# power.net
KiCad netlist of a schematic drawn in EAGLE
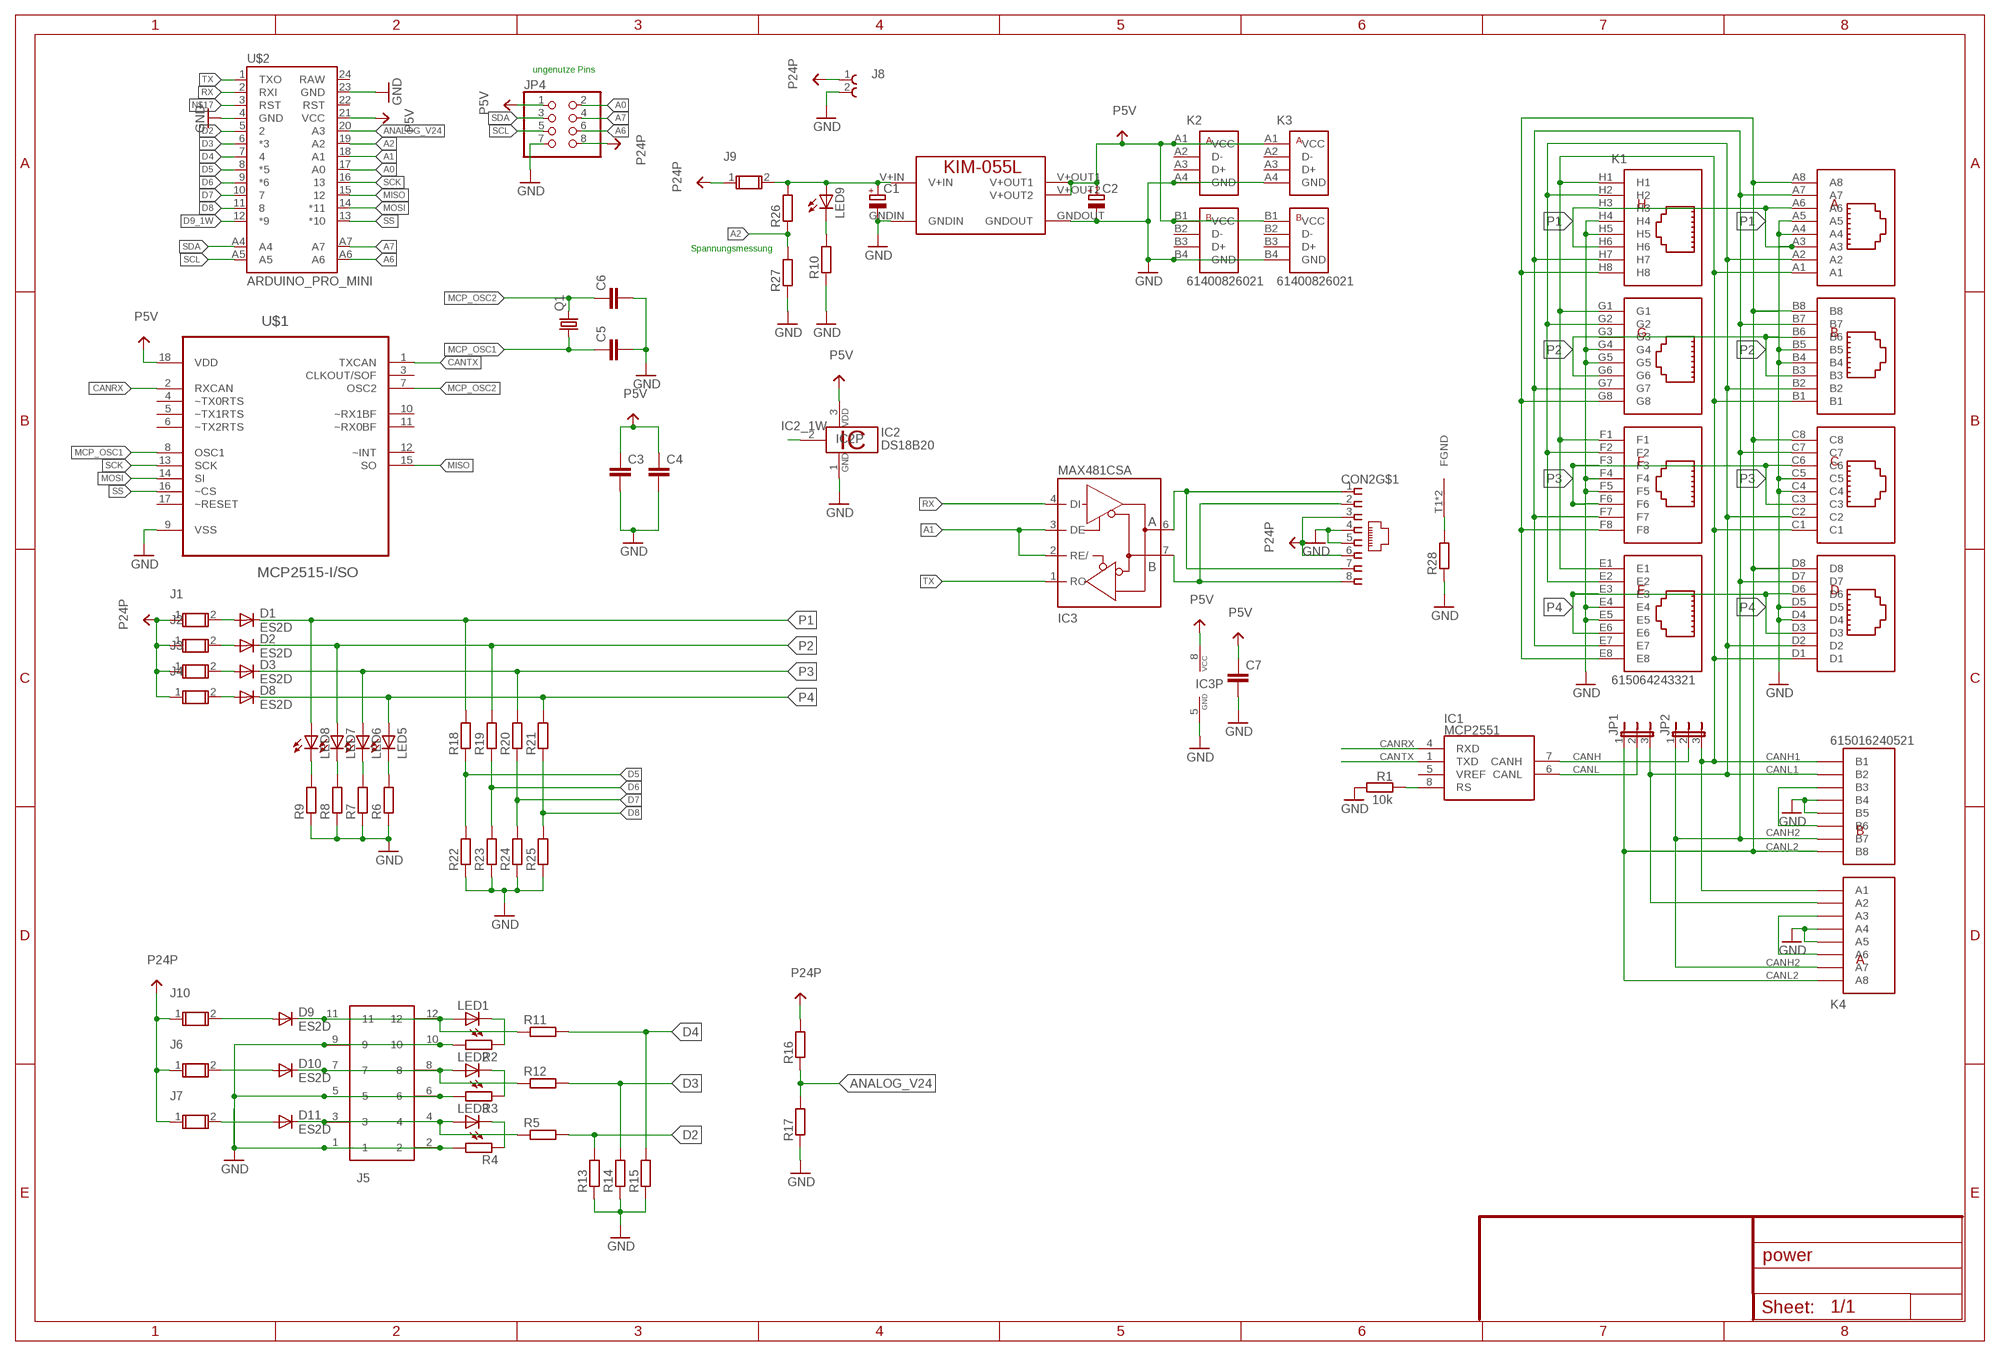
[diagram p0: schematic, sheet 1]

(export (version "E")
  (design (tool "Eeschema 10.0.6"))
  (components
    (comp (ref "C1")
      (value "CPOL-EUE5-10.5")
      (footprint "eagle-import:E5-10,5")
      (libsource (lib "eagle-import") (part "CPOL-EUE5-10.5"))
    )
    (comp (ref "C2")
      (value "CPOL-EUE5-10.5")
      (footprint "eagle-import:E5-10,5")
      (libsource (lib "eagle-import") (part "CPOL-EUE5-10.5"))
    )
    (comp (ref "C3")
      (value "C-EUC0805")
      (footprint "eagle-import:C0805")
      (libsource (lib "eagle-import") (part "C-EUC0805"))
    )
    (comp (ref "C4")
      (value "C-EUC0805")
      (footprint "eagle-import:C0805")
      (libsource (lib "eagle-import") (part "C-EUC0805"))
    )
    (comp (ref "C5")
      (value "C-EUC0805")
      (footprint "eagle-import:C0805")
      (libsource (lib "eagle-import") (part "C-EUC0805"))
    )
    (comp (ref "C6")
      (value "C-EUC0805")
      (footprint "eagle-import:C0805")
      (libsource (lib "eagle-import") (part "C-EUC0805"))
    )
    (comp (ref "C7")
      (value "C-EUC0805")
      (footprint "eagle-import:C0805")
      (libsource (lib "eagle-import") (part "C-EUC0805"))
    )
    (comp (ref "CON2")
      (value "MEBP_8-8G")
      (footprint "eagle-import:MEBP")
      (libsource (lib "eagle-import") (part "MEBP_8-8G"))
    )
    (comp (ref "D1")
      (value "ES2D")
      (footprint "eagle-import:SMB")
      (libsource (lib "eagle-import") (part "ES2D"))
    )
    (comp (ref "D2")
      (value "ES2D")
      (footprint "eagle-import:SMB")
      (libsource (lib "eagle-import") (part "ES2D"))
    )
    (comp (ref "D3")
      (value "ES2D")
      (footprint "eagle-import:SMB")
      (libsource (lib "eagle-import") (part "ES2D"))
    )
    (comp (ref "D8")
      (value "ES2D")
      (footprint "eagle-import:SMB")
      (libsource (lib "eagle-import") (part "ES2D"))
    )
    (comp (ref "D9")
      (value "ES2D")
      (footprint "eagle-import:SMB")
      (libsource (lib "eagle-import") (part "ES2D"))
    )
    (comp (ref "D10")
      (value "ES2D")
      (footprint "eagle-import:SMB")
      (libsource (lib "eagle-import") (part "ES2D"))
    )
    (comp (ref "D11")
      (value "ES2D")
      (footprint "eagle-import:SMB")
      (libsource (lib "eagle-import") (part "ES2D"))
    )
    (comp (ref "IC1")
      (value "MCP2551")
      (footprint "eagle-import:SO-8")
      (libsource (lib "eagle-import") (part "MCP2551"))
    )
    (comp (ref "IC2")
      (value "DS18B20")
      (footprint "eagle-import:TO92-")
      (libsource (lib "eagle-import") (part "DS18B20"))
    )
    (comp (ref "IC3")
      (value "MAX481CSA")
      (footprint "eagle-import:SO08")
      (fields (field (name "MF") "MAXIM"))
      (libsource (lib "eagle-import") (part "MAX481CSA"))
    )
    (comp (ref "J1")
      (value "696101000002")
      (footprint "eagle-import:696101000002")
      (libsource (lib "eagle-import") (part "696101000002"))
    )
    (comp (ref "J2")
      (value "696101000002")
      (footprint "eagle-import:696101000002")
      (libsource (lib "eagle-import") (part "696101000002"))
    )
    (comp (ref "J3")
      (value "696101000002")
      (footprint "eagle-import:696101000002")
      (libsource (lib "eagle-import") (part "696101000002"))
    )
    (comp (ref "J4")
      (value "696101000002")
      (footprint "eagle-import:696101000002")
      (libsource (lib "eagle-import") (part "696101000002"))
    )
    (comp (ref "J5")
      (value "691332510012")
      (footprint "eagle-import:691332510012")
      (libsource (lib "eagle-import") (part "691332510012"))
    )
    (comp (ref "J6")
      (value "696101000002")
      (footprint "eagle-import:696101000002")
      (libsource (lib "eagle-import") (part "696101000002"))
    )
    (comp (ref "J7")
      (value "696101000002")
      (footprint "eagle-import:696101000002")
      (libsource (lib "eagle-import") (part "696101000002"))
    )
    (comp (ref "J8")
      (value "691312510002")
      (footprint "eagle-import:691312510002")
      (libsource (lib "eagle-import") (part "691312510002"))
    )
    (comp (ref "J9")
      (value "696101000002")
      (footprint "eagle-import:696101000002")
      (libsource (lib "eagle-import") (part "696101000002"))
    )
    (comp (ref "J10")
      (value "696101000002")
      (footprint "eagle-import:696101000002")
      (libsource (lib "eagle-import") (part "696101000002"))
    )
    (comp (ref "JP1")
      (value "JP2E")
      (footprint "eagle-import:JP2")
      (libsource (lib "eagle-import") (part "JP2E"))
    )
    (comp (ref "JP2")
      (value "JP2E")
      (footprint "eagle-import:JP2")
      (libsource (lib "eagle-import") (part "JP2E"))
    )
    (comp (ref "JP4")
      (value "PINHD-2X4")
      (footprint "eagle-import:2X04")
      (libsource (lib "eagle-import") (part "PINHD-2X4"))
    )
    (comp (ref "K1")
      (value "615064243321")
      (footprint "eagle-import:615064243321")
      (libsource (lib "eagle-import") (part "615064243321"))
    )
    (comp (ref "K2")
      (value "61400826021")
      (footprint "eagle-import:61400826021")
      (libsource (lib "eagle-import") (part "61400826021"))
    )
    (comp (ref "K3")
      (value "61400826021")
      (footprint "eagle-import:61400826021")
      (libsource (lib "eagle-import") (part "61400826021"))
    )
    (comp (ref "K4")
      (value "615016240521")
      (footprint "eagle-import:615016240521")
      (libsource (lib "eagle-import") (part "615016240521"))
    )
    (comp (ref "LED1")
      (value "LED3MM")
      (footprint "eagle-import:LED3MM")
      (libsource (lib "eagle-import") (part "LED3MM"))
    )
    (comp (ref "LED2")
      (value "LED3MM")
      (footprint "eagle-import:LED3MM")
      (libsource (lib "eagle-import") (part "LED3MM"))
    )
    (comp (ref "LED3")
      (value "LED3MM")
      (footprint "eagle-import:LED3MM")
      (libsource (lib "eagle-import") (part "LED3MM"))
    )
    (comp (ref "LED5")
      (value "LED3MM")
      (footprint "eagle-import:LED3MM")
      (libsource (lib "eagle-import") (part "LED3MM"))
    )
    (comp (ref "LED6")
      (value "LED3MM")
      (footprint "eagle-import:LED3MM")
      (libsource (lib "eagle-import") (part "LED3MM"))
    )
    (comp (ref "LED7")
      (value "LED3MM")
      (footprint "eagle-import:LED3MM")
      (libsource (lib "eagle-import") (part "LED3MM"))
    )
    (comp (ref "LED8")
      (value "LED3MM")
      (footprint "eagle-import:LED3MM")
      (libsource (lib "eagle-import") (part "LED3MM"))
    )
    (comp (ref "LED9")
      (value "LED3MM")
      (footprint "eagle-import:LED3MM")
      (libsource (lib "eagle-import") (part "LED3MM"))
    )
    (comp (ref "MOD1")
      (value "KIM-055L")
      (footprint "eagle-import:KIM-055L")
      (libsource (lib "eagle-import") (part "KIM-055L"))
    )
    (comp (ref "Q1")
      (value "CRYSTALHC49S")
      (footprint "eagle-import:HC49_S")
      (libsource (lib "eagle-import") (part "CRYSTALHC49S"))
    )
    (comp (ref "R1")
      (value "10k")
      (footprint "eagle-import:R0603")
      (libsource (lib "eagle-import") (part "R-EU_R0603"))
    )
    (comp (ref "R2")
      (value "R-EU_R0805")
      (footprint "eagle-import:R0805")
      (libsource (lib "eagle-import") (part "schlager_passiv_R-EU_R0805"))
    )
    (comp (ref "R3")
      (value "R-EU_R0805")
      (footprint "eagle-import:R0805")
      (libsource (lib "eagle-import") (part "schlager_passiv_R-EU_R0805"))
    )
    (comp (ref "R4")
      (value "R-EU_R0805")
      (footprint "eagle-import:R0805")
      (libsource (lib "eagle-import") (part "schlager_passiv_R-EU_R0805"))
    )
    (comp (ref "R5")
      (value "R-EU_R0805")
      (footprint "eagle-import:R0805")
      (libsource (lib "eagle-import") (part "schlager_passiv_R-EU_R0805"))
    )
    (comp (ref "R6")
      (value "R-EU_R0805")
      (footprint "eagle-import:R0805")
      (libsource (lib "eagle-import") (part "schlager_passiv_R-EU_R0805"))
    )
    (comp (ref "R7")
      (value "R-EU_R0805")
      (footprint "eagle-import:R0805")
      (libsource (lib "eagle-import") (part "schlager_passiv_R-EU_R0805"))
    )
    (comp (ref "R8")
      (value "R-EU_R0805")
      (footprint "eagle-import:R0805")
      (libsource (lib "eagle-import") (part "schlager_passiv_R-EU_R0805"))
    )
    (comp (ref "R9")
      (value "R-EU_R0805")
      (footprint "eagle-import:R0805")
      (libsource (lib "eagle-import") (part "schlager_passiv_R-EU_R0805"))
    )
    (comp (ref "R10")
      (value "R-EU_R0805")
      (footprint "eagle-import:R0805")
      (libsource (lib "eagle-import") (part "schlager_passiv_R-EU_R0805"))
    )
    (comp (ref "R11")
      (value "R-EU_R0805")
      (footprint "eagle-import:R0805")
      (libsource (lib "eagle-import") (part "schlager_passiv_R-EU_R0805"))
    )
    (comp (ref "R12")
      (value "R-EU_R0805")
      (footprint "eagle-import:R0805")
      (libsource (lib "eagle-import") (part "schlager_passiv_R-EU_R0805"))
    )
    (comp (ref "R13")
      (value "R-EU_R0805")
      (footprint "eagle-import:R0805")
      (libsource (lib "eagle-import") (part "schlager_passiv_R-EU_R0805"))
    )
    (comp (ref "R14")
      (value "R-EU_R0805")
      (footprint "eagle-import:R0805")
      (libsource (lib "eagle-import") (part "schlager_passiv_R-EU_R0805"))
    )
    (comp (ref "R15")
      (value "R-EU_R0805")
      (footprint "eagle-import:R0805")
      (libsource (lib "eagle-import") (part "schlager_passiv_R-EU_R0805"))
    )
    (comp (ref "R16")
      (value "R-EU_R0805")
      (footprint "eagle-import:R0805")
      (libsource (lib "eagle-import") (part "schlager_passiv_R-EU_R0805"))
    )
    (comp (ref "R17")
      (value "R-EU_R0805")
      (footprint "eagle-import:R0805")
      (libsource (lib "eagle-import") (part "schlager_passiv_R-EU_R0805"))
    )
    (comp (ref "R18")
      (value "R-EU_R0805")
      (footprint "eagle-import:R0805")
      (libsource (lib "eagle-import") (part "schlager_passiv_R-EU_R0805"))
    )
    (comp (ref "R19")
      (value "R-EU_R0805")
      (footprint "eagle-import:R0805")
      (libsource (lib "eagle-import") (part "schlager_passiv_R-EU_R0805"))
    )
    (comp (ref "R20")
      (value "R-EU_R0805")
      (footprint "eagle-import:R0805")
      (libsource (lib "eagle-import") (part "schlager_passiv_R-EU_R0805"))
    )
    (comp (ref "R21")
      (value "R-EU_R0805")
      (footprint "eagle-import:R0805")
      (libsource (lib "eagle-import") (part "schlager_passiv_R-EU_R0805"))
    )
    (comp (ref "R22")
      (value "R-EU_R0805")
      (footprint "eagle-import:R0805")
      (libsource (lib "eagle-import") (part "schlager_passiv_R-EU_R0805"))
    )
    (comp (ref "R23")
      (value "R-EU_R0805")
      (footprint "eagle-import:R0805")
      (libsource (lib "eagle-import") (part "schlager_passiv_R-EU_R0805"))
    )
    (comp (ref "R24")
      (value "R-EU_R0805")
      (footprint "eagle-import:R0805")
      (libsource (lib "eagle-import") (part "schlager_passiv_R-EU_R0805"))
    )
    (comp (ref "R25")
      (value "R-EU_R0805")
      (footprint "eagle-import:R0805")
      (libsource (lib "eagle-import") (part "schlager_passiv_R-EU_R0805"))
    )
    (comp (ref "R26")
      (value "R-EU_R0805")
      (footprint "eagle-import:R0805")
      (libsource (lib "eagle-import") (part "schlager_passiv_R-EU_R0805"))
    )
    (comp (ref "R27")
      (value "R-EU_R0805")
      (footprint "eagle-import:R0805")
      (libsource (lib "eagle-import") (part "schlager_passiv_R-EU_R0805"))
    )
    (comp (ref "R28")
      (value "R-EU_R0805")
      (footprint "eagle-import:R0805")
      (libsource (lib "eagle-import") (part "schlager_passiv_R-EU_R0805"))
    )
    (comp (ref "U$1")
      (value "MCP2515-I/SO")
      (footprint "eagle-import:SOIC127P1034X264-18N")
      (libsource (lib "eagle-import") (part "MCP2515-I/SO"))
    )
    (comp (ref "U$2")
      (value "ARDUINO_PRO_MINI")
      (footprint "eagle-import:ARDUINO_PRO_MINI")
      (libsource (lib "eagle-import") (part "ARDUINO_PRO_MINI"))
    )
  )
  (nets
    (net (code "1") (name "/CANH") (class "Default")
      (node (ref "IC1") (pin "7") (pinfunction "CANH_7") (pintype "bidirectional"))
      (node (ref "JP2") (pin "2") (pinfunction "2_2") (pintype "passive"))
    )
    (net (code "2") (name "/CANH1") (class "Default")
      (node (ref "JP2") (pin "3") (pinfunction "3_3") (pintype "passive"))
      (node (ref "K1") (pin "A1") (pinfunction "A1_A1") (pintype "passive"))
      (node (ref "K1") (pin "B1") (pinfunction "B1_B1") (pintype "passive"))
      (node (ref "K1") (pin "C1") (pinfunction "C1_C1") (pintype "passive"))
      (node (ref "K1") (pin "D1") (pinfunction "D1_D1") (pintype "passive"))
      (node (ref "K1") (pin "E1") (pinfunction "E1_E1") (pintype "passive"))
      (node (ref "K1") (pin "F1") (pinfunction "F1_F1") (pintype "passive"))
      (node (ref "K1") (pin "G1") (pinfunction "G1_G1") (pintype "passive"))
      (node (ref "K1") (pin "H1") (pinfunction "H1_H1") (pintype "passive"))
      (node (ref "K4") (pin "A1") (pinfunction "A1_A1") (pintype "passive"))
      (node (ref "K4") (pin "B1") (pinfunction "B1_B1") (pintype "passive"))
    )
    (net (code "3") (name "/CANH2") (class "Default")
      (node (ref "JP2") (pin "1") (pinfunction "1_1") (pintype "passive"))
      (node (ref "K1") (pin "A7") (pinfunction "A7_A7") (pintype "passive"))
      (node (ref "K1") (pin "B7") (pinfunction "B7_B7") (pintype "passive"))
      (node (ref "K1") (pin "C7") (pinfunction "C7_C7") (pintype "passive"))
      (node (ref "K1") (pin "D7") (pinfunction "D7_D7") (pintype "passive"))
      (node (ref "K1") (pin "E7") (pinfunction "E7_E7") (pintype "passive"))
      (node (ref "K1") (pin "F7") (pinfunction "F7_F7") (pintype "passive"))
      (node (ref "K1") (pin "G7") (pinfunction "G7_G7") (pintype "passive"))
      (node (ref "K1") (pin "H7") (pinfunction "H7_H7") (pintype "passive"))
      (node (ref "K4") (pin "A7") (pinfunction "A7_A7") (pintype "passive"))
      (node (ref "K4") (pin "B7") (pinfunction "B7_B7") (pintype "passive"))
    )
    (net (code "4") (name "/CANL") (class "Default")
      (node (ref "IC1") (pin "6") (pinfunction "CANL_6") (pintype "bidirectional"))
      (node (ref "JP1") (pin "2") (pinfunction "2_2") (pintype "passive"))
    )
    (net (code "5") (name "/CANL1") (class "Default")
      (node (ref "JP1") (pin "3") (pinfunction "3_3") (pintype "passive"))
      (node (ref "K1") (pin "A2") (pinfunction "A2_A2") (pintype "passive"))
      (node (ref "K1") (pin "B2") (pinfunction "B2_B2") (pintype "passive"))
      (node (ref "K1") (pin "C2") (pinfunction "C2_C2") (pintype "passive"))
      (node (ref "K1") (pin "D2") (pinfunction "D2_D2") (pintype "passive"))
      (node (ref "K1") (pin "E2") (pinfunction "E2_E2") (pintype "passive"))
      (node (ref "K1") (pin "F2") (pinfunction "F2_F2") (pintype "passive"))
      (node (ref "K1") (pin "G2") (pinfunction "G2_G2") (pintype "passive"))
      (node (ref "K1") (pin "H2") (pinfunction "H2_H2") (pintype "passive"))
      (node (ref "K4") (pin "A2") (pinfunction "A2_A2") (pintype "passive"))
      (node (ref "K4") (pin "B2") (pinfunction "B2_B2") (pintype "passive"))
    )
    (net (code "6") (name "/CANL2") (class "Default")
      (node (ref "JP1") (pin "1") (pinfunction "1_1") (pintype "passive"))
      (node (ref "K1") (pin "A8") (pinfunction "A8_A8") (pintype "passive"))
      (node (ref "K1") (pin "B8") (pinfunction "B8_B8") (pintype "passive"))
      (node (ref "K1") (pin "C8") (pinfunction "C8_C8") (pintype "passive"))
      (node (ref "K1") (pin "D8") (pinfunction "D8_D8") (pintype "passive"))
      (node (ref "K1") (pin "E8") (pinfunction "E8_E8") (pintype "passive"))
      (node (ref "K1") (pin "F8") (pinfunction "F8_F8") (pintype "passive"))
      (node (ref "K1") (pin "G8") (pinfunction "G8_G8") (pintype "passive"))
      (node (ref "K1") (pin "H8") (pinfunction "H8_H8") (pintype "passive"))
      (node (ref "K4") (pin "A8") (pinfunction "A8_A8") (pintype "passive"))
      (node (ref "K4") (pin "B8") (pinfunction "B8_B8") (pintype "passive"))
    )
    (net (code "7") (name "A0") (class "Default")
      (node (ref "JP4") (pin "2") (pinfunction "2_2") (pintype "passive"))
      (node (ref "U$2") (pin "17") (pinfunction "A0_17") (pintype "bidirectional"))
    )
    (net (code "8") (name "A1") (class "Default")
      (node (ref "IC3") (pin "2") (pinfunction "RE/_2") (pintype "input"))
      (node (ref "IC3") (pin "3") (pinfunction "DE_3") (pintype "input"))
      (node (ref "U$2") (pin "18") (pinfunction "A1_18") (pintype "bidirectional"))
    )
    (net (code "9") (name "A2") (class "Default")
      (node (ref "R26") (pin "1") (pinfunction "1_1") (pintype "passive"))
      (node (ref "R27") (pin "2") (pinfunction "2_2") (pintype "passive"))
      (node (ref "U$2") (pin "19") (pinfunction "A2_19") (pintype "bidirectional"))
    )
    (net (code "10") (name "A6") (class "Default")
      (node (ref "JP4") (pin "6") (pinfunction "6_6") (pintype "passive"))
      (node (ref "U$2") (pin "A6") (pinfunction "A6_A6") (pintype "bidirectional"))
    )
    (net (code "11") (name "A7") (class "Default")
      (node (ref "JP4") (pin "4") (pinfunction "4_4") (pintype "passive"))
      (node (ref "U$2") (pin "A7") (pinfunction "A7_A7") (pintype "bidirectional"))
    )
    (net (code "12") (name "ANALOG_V24") (class "Default")
      (node (ref "R16") (pin "1") (pinfunction "1_1") (pintype "passive"))
      (node (ref "R17") (pin "2") (pinfunction "2_2") (pintype "passive"))
      (node (ref "U$2") (pin "20") (pinfunction "A3_20") (pintype "bidirectional"))
    )
    (net (code "13") (name "CANRX") (class "Default")
      (node (ref "IC1") (pin "4") (pinfunction "RXD_4") (pintype "bidirectional"))
      (node (ref "U$1") (pin "2") (pinfunction "RXCAN_2") (pintype "input"))
    )
    (net (code "14") (name "CANTX") (class "Default")
      (node (ref "IC1") (pin "1") (pinfunction "TXD_1") (pintype "bidirectional"))
      (node (ref "U$1") (pin "1") (pinfunction "TXCAN_1") (pintype "output"))
    )
    (net (code "15") (name "D2") (class "Default")
      (node (ref "R13") (pin "2") (pinfunction "2_2") (pintype "passive"))
      (node (ref "R5") (pin "2") (pinfunction "2_2") (pintype "passive"))
      (node (ref "U$2") (pin "5") (pinfunction "2_5") (pintype "bidirectional"))
    )
    (net (code "16") (name "D3") (class "Default")
      (node (ref "R12") (pin "2") (pinfunction "2_2") (pintype "passive"))
      (node (ref "R14") (pin "2") (pinfunction "2_2") (pintype "passive"))
      (node (ref "U$2") (pin "6") (pinfunction "*3_6") (pintype "bidirectional"))
    )
    (net (code "17") (name "D4") (class "Default")
      (node (ref "R11") (pin "2") (pinfunction "2_2") (pintype "passive"))
      (node (ref "R15") (pin "2") (pinfunction "2_2") (pintype "passive"))
      (node (ref "U$2") (pin "7") (pinfunction "4_7") (pintype "bidirectional"))
    )
    (net (code "18") (name "D5") (class "Default")
      (node (ref "R18") (pin "1") (pinfunction "1_1") (pintype "passive"))
      (node (ref "R22") (pin "2") (pinfunction "2_2") (pintype "passive"))
      (node (ref "U$2") (pin "8") (pinfunction "*5_8") (pintype "bidirectional"))
    )
    (net (code "19") (name "D6") (class "Default")
      (node (ref "R19") (pin "1") (pinfunction "1_1") (pintype "passive"))
      (node (ref "R23") (pin "2") (pinfunction "2_2") (pintype "passive"))
      (node (ref "U$2") (pin "9") (pinfunction "*6_9") (pintype "bidirectional"))
    )
    (net (code "20") (name "D7") (class "Default")
      (node (ref "R20") (pin "1") (pinfunction "1_1") (pintype "passive"))
      (node (ref "R24") (pin "2") (pinfunction "2_2") (pintype "passive"))
      (node (ref "U$2") (pin "10") (pinfunction "7_10") (pintype "bidirectional"))
    )
    (net (code "21") (name "D8") (class "Default")
      (node (ref "R21") (pin "1") (pinfunction "1_1") (pintype "passive"))
      (node (ref "R25") (pin "2") (pinfunction "2_2") (pintype "passive"))
      (node (ref "U$2") (pin "11") (pinfunction "8_11") (pintype "bidirectional"))
    )
    (net (code "22") (name "D9_1W") (class "Default")
      (node (ref "IC2") (pin "2") (pinfunction "1W_2") (pintype "power_in"))
      (node (ref "U$2") (pin "12") (pinfunction "*9_12") (pintype "bidirectional"))
    )
    (net (code "23") (name "GND") (class "Default")
      (node (ref "C1") (pin "-") (pinfunction "-_-") (pintype "passive"))
      (node (ref "C2") (pin "-") (pinfunction "-_-") (pintype "passive"))
      (node (ref "C3") (pin "2") (pinfunction "2_2") (pintype "passive"))
      (node (ref "C4") (pin "2") (pinfunction "2_2") (pintype "passive"))
      (node (ref "C5") (pin "2") (pinfunction "2_2") (pintype "passive"))
      (node (ref "C6") (pin "2") (pinfunction "2_2") (pintype "passive"))
      (node (ref "C7") (pin "2") (pinfunction "2_2") (pintype "passive"))
      (node (ref "CON2") (pin "4") (pinfunction "4_4") (pintype "passive"))
      (node (ref "CON2") (pin "5") (pinfunction "5_5") (pintype "passive"))
      (node (ref "IC2") (pin "1") (pinfunction "GND_1") (pintype "power_in"))
      (node (ref "IC3") (pin "5") (pinfunction "GND_5") (pintype "power_in"))
      (node (ref "J5") (pin "1") (pinfunction "1_1") (pintype "passive"))
      (node (ref "J5") (pin "10") (pinfunction "10_10") (pintype "passive"))
      (node (ref "J5") (pin "2") (pinfunction "2_2") (pintype "passive"))
      (node (ref "J5") (pin "5") (pinfunction "5_5") (pintype "passive"))
      (node (ref "J5") (pin "6") (pinfunction "6_6") (pintype "passive"))
      (node (ref "J5") (pin "9") (pinfunction "9_9") (pintype "passive"))
      (node (ref "J8") (pin "2") (pinfunction "2_2") (pintype "passive"))
      (node (ref "JP4") (pin "7") (pinfunction "7_7") (pintype "passive"))
      (node (ref "K1") (pin "A4") (pinfunction "A4_A4") (pintype "passive"))
      (node (ref "K1") (pin "A5") (pinfunction "A5_A5") (pintype "passive"))
      (node (ref "K1") (pin "B4") (pinfunction "B4_B4") (pintype "passive"))
      (node (ref "K1") (pin "B5") (pinfunction "B5_B5") (pintype "passive"))
      (node (ref "K1") (pin "C4") (pinfunction "C4_C4") (pintype "passive"))
      (node (ref "K1") (pin "C5") (pinfunction "C5_C5") (pintype "passive"))
      (node (ref "K1") (pin "D4") (pinfunction "D4_D4") (pintype "passive"))
      (node (ref "K1") (pin "D5") (pinfunction "D5_D5") (pintype "passive"))
      (node (ref "K1") (pin "E4") (pinfunction "E4_E4") (pintype "passive"))
      (node (ref "K1") (pin "E5") (pinfunction "E5_E5") (pintype "passive"))
      (node (ref "K1") (pin "F4") (pinfunction "F4_F4") (pintype "passive"))
      (node (ref "K1") (pin "F5") (pinfunction "F5_F5") (pintype "passive"))
      (node (ref "K1") (pin "G4") (pinfunction "G4_G4") (pintype "passive"))
      (node (ref "K1") (pin "G5") (pinfunction "G5_G5") (pintype "passive"))
      (node (ref "K1") (pin "H4") (pinfunction "H4_H4") (pintype "passive"))
      (node (ref "K1") (pin "H5") (pinfunction "H5_H5") (pintype "passive"))
      (node (ref "K2") (pin "A4") (pinfunction "GND_A4") (pintype "bidirectional"))
      (node (ref "K2") (pin "B4") (pinfunction "GND_B4") (pintype "bidirectional"))
      (node (ref "K3") (pin "A4") (pinfunction "GND_A4") (pintype "bidirectional"))
      (node (ref "K3") (pin "B4") (pinfunction "GND_B4") (pintype "bidirectional"))
      (node (ref "K4") (pin "A4") (pinfunction "A4_A4") (pintype "passive"))
      (node (ref "K4") (pin "A5") (pinfunction "A5_A5") (pintype "passive"))
      (node (ref "K4") (pin "B4") (pinfunction "B4_B4") (pintype "passive"))
      (node (ref "K4") (pin "B5") (pinfunction "B5_B5") (pintype "passive"))
      (node (ref "MOD1") (pin "GNDIN") (pinfunction "GNDIN_GNDIN") (pintype "bidirectional"))
      (node (ref "MOD1") (pin "GNDOUT") (pinfunction "GNDOUT_GNDOUT") (pintype "bidirectional"))
      (node (ref "R1") (pin "2") (pinfunction "2_2") (pintype "passive"))
      (node (ref "R10") (pin "1") (pinfunction "1_1") (pintype "passive"))
      (node (ref "R13") (pin "1") (pinfunction "1_1") (pintype "passive"))
      (node (ref "R14") (pin "1") (pinfunction "1_1") (pintype "passive"))
      (node (ref "R15") (pin "1") (pinfunction "1_1") (pintype "passive"))
      (node (ref "R17") (pin "1") (pinfunction "1_1") (pintype "passive"))
      (node (ref "R2") (pin "2") (pinfunction "2_2") (pintype "passive"))
      (node (ref "R22") (pin "1") (pinfunction "1_1") (pintype "passive"))
      (node (ref "R23") (pin "1") (pinfunction "1_1") (pintype "passive"))
      (node (ref "R24") (pin "1") (pinfunction "1_1") (pintype "passive"))
      (node (ref "R25") (pin "1") (pinfunction "1_1") (pintype "passive"))
      (node (ref "R27") (pin "1") (pinfunction "1_1") (pintype "passive"))
      (node (ref "R28") (pin "1") (pinfunction "1_1") (pintype "passive"))
      (node (ref "R3") (pin "2") (pinfunction "2_2") (pintype "passive"))
      (node (ref "R4") (pin "2") (pinfunction "2_2") (pintype "passive"))
      (node (ref "R6") (pin "1") (pinfunction "1_1") (pintype "passive"))
      (node (ref "R7") (pin "1") (pinfunction "1_1") (pintype "passive"))
      (node (ref "R8") (pin "1") (pinfunction "1_1") (pintype "passive"))
      (node (ref "R9") (pin "1") (pinfunction "1_1") (pintype "passive"))
      (node (ref "U$1") (pin "9") (pinfunction "VSS_9") (pintype "power_in"))
      (node (ref "U$2") (pin "23") (pinfunction "GND_23") (pintype "bidirectional"))
      (node (ref "U$2") (pin "4") (pinfunction "GND_4") (pintype "bidirectional"))
    )
    (net (code "24") (name "MCP_OSC1") (class "Default")
      (node (ref "C5") (pin "1") (pinfunction "1_1") (pintype "passive"))
      (node (ref "Q1") (pin "1") (pinfunction "1_1") (pintype "passive"))
      (node (ref "U$1") (pin "8") (pinfunction "OSC1_8") (pintype "input"))
    )
    (net (code "25") (name "MCP_OSC2") (class "Default")
      (node (ref "C6") (pin "1") (pinfunction "1_1") (pintype "passive"))
      (node (ref "Q1") (pin "2") (pinfunction "2_2") (pintype "passive"))
      (node (ref "U$1") (pin "7") (pinfunction "OSC2_7") (pintype "output"))
    )
    (net (code "26") (name "MISO") (class "Default")
      (node (ref "U$1") (pin "15") (pinfunction "SO_15") (pintype "output"))
      (node (ref "U$2") (pin "15") (pinfunction "12_15") (pintype "bidirectional"))
    )
    (net (code "27") (name "MOSI") (class "Default")
      (node (ref "U$1") (pin "14") (pinfunction "SI_14") (pintype "input"))
      (node (ref "U$2") (pin "14") (pinfunction "*11_14") (pintype "bidirectional"))
    )
    (net (code "28") (name "N$17") (class "Default")
      (node (ref "U$2") (pin "3") (pinfunction "RST_3") (pintype "bidirectional"))
    )
    (net (code "29") (name "Net-(C1-Pad+)") (class "Default")
      (node (ref "C1") (pin "+") (pinfunction "+_+") (pintype "passive"))
      (node (ref "J9") (pin "2") (pinfunction "2_2") (pintype "passive"))
      (node (ref "LED9") (pin "A") (pinfunction "A_A") (pintype "passive"))
      (node (ref "MOD1") (pin "V+IN") (pinfunction "V+IN_V+IN") (pintype "bidirectional"))
      (node (ref "R26") (pin "2") (pinfunction "2_2") (pintype "passive"))
    )
    (net (code "30") (name "Net-(CON2B-FGND-PadT1)") (class "Default")
      (node (ref "CON2") (pin "T1") (pinfunction "FGND_T1") (pintype "power_in"))
      (node (ref "CON2") (pin "T2") (pinfunction "FGND_T2") (pintype "power_in"))
      (node (ref "R28") (pin "2") (pinfunction "2_2") (pintype "passive"))
    )
    (net (code "31") (name "Net-(D1-PadA)") (class "Default")
      (node (ref "D1") (pin "A") (pinfunction "A_A") (pintype "passive"))
      (node (ref "J1") (pin "2") (pinfunction "2_2") (pintype "passive"))
    )
    (net (code "32") (name "Net-(D2-PadA)") (class "Default")
      (node (ref "D2") (pin "A") (pinfunction "A_A") (pintype "passive"))
      (node (ref "J2") (pin "2") (pinfunction "2_2") (pintype "passive"))
    )
    (net (code "33") (name "Net-(D3-PadA)") (class "Default")
      (node (ref "D3") (pin "A") (pinfunction "A_A") (pintype "passive"))
      (node (ref "J3") (pin "2") (pinfunction "2_2") (pintype "passive"))
    )
    (net (code "34") (name "Net-(D8-PadA)") (class "Default")
      (node (ref "D8") (pin "A") (pinfunction "A_A") (pintype "passive"))
      (node (ref "J4") (pin "2") (pinfunction "2_2") (pintype "passive"))
    )
    (net (code "35") (name "Net-(D9-PadA)") (class "Default")
      (node (ref "D9") (pin "A") (pinfunction "A_A") (pintype "passive"))
      (node (ref "J10") (pin "2") (pinfunction "2_2") (pintype "passive"))
    )
    (net (code "36") (name "Net-(D9-PadC)") (class "Default")
      (node (ref "D9") (pin "C") (pinfunction "C_C") (pintype "passive"))
      (node (ref "J5") (pin "11") (pinfunction "11_11") (pintype "passive"))
      (node (ref "J5") (pin "12") (pinfunction "12_12") (pintype "passive"))
      (node (ref "LED1") (pin "A") (pinfunction "A_A") (pintype "passive"))
      (node (ref "R11") (pin "1") (pinfunction "1_1") (pintype "passive"))
    )
    (net (code "37") (name "Net-(D10-PadA)") (class "Default")
      (node (ref "D10") (pin "A") (pinfunction "A_A") (pintype "passive"))
      (node (ref "J6") (pin "2") (pinfunction "2_2") (pintype "passive"))
    )
    (net (code "38") (name "Net-(D10-PadC)") (class "Default")
      (node (ref "D10") (pin "C") (pinfunction "C_C") (pintype "passive"))
      (node (ref "J5") (pin "7") (pinfunction "7_7") (pintype "passive"))
      (node (ref "J5") (pin "8") (pinfunction "8_8") (pintype "passive"))
      (node (ref "LED2") (pin "A") (pinfunction "A_A") (pintype "passive"))
      (node (ref "R12") (pin "1") (pinfunction "1_1") (pintype "passive"))
    )
    (net (code "39") (name "Net-(D11-PadA)") (class "Default")
      (node (ref "D11") (pin "A") (pinfunction "A_A") (pintype "passive"))
      (node (ref "J7") (pin "2") (pinfunction "2_2") (pintype "passive"))
    )
    (net (code "40") (name "Net-(D11-PadC)") (class "Default")
      (node (ref "D11") (pin "C") (pinfunction "C_C") (pintype "passive"))
      (node (ref "J5") (pin "3") (pinfunction "3_3") (pintype "passive"))
      (node (ref "J5") (pin "4") (pinfunction "4_4") (pintype "passive"))
      (node (ref "LED3") (pin "A") (pinfunction "A_A") (pintype "passive"))
      (node (ref "R5") (pin "1") (pinfunction "1_1") (pintype "passive"))
    )
    (net (code "41") (name "Net-(IC1A-RS)") (class "Default")
      (node (ref "IC1") (pin "8") (pinfunction "RS_8") (pintype "bidirectional"))
      (node (ref "R1") (pin "1") (pinfunction "1_1") (pintype "passive"))
    )
    (net (code "42") (name "Net-(IC3A-A)") (class "Default")
      (node (ref "CON2") (pin "1") (pinfunction "1_1") (pintype "passive"))
      (node (ref "CON2") (pin "7") (pinfunction "7_7") (pintype "passive"))
      (node (ref "IC3") (pin "6") (pinfunction "A_6") (pintype "passive"))
    )
    (net (code "43") (name "Net-(IC3A-B)") (class "Default")
      (node (ref "CON2") (pin "2") (pinfunction "2_2") (pintype "passive"))
      (node (ref "CON2") (pin "8") (pinfunction "8_8") (pintype "passive"))
      (node (ref "IC3") (pin "7") (pinfunction "B_7") (pintype "passive"))
    )
    (net (code "44") (name "Net-(K4-PadA3)") (class "Default")
      (node (ref "K4") (pin "A3") (pinfunction "A3_A3") (pintype "passive"))
      (node (ref "K4") (pin "A6") (pinfunction "A6_A6") (pintype "passive"))
    )
    (net (code "45") (name "Net-(K4-PadB3)") (class "Default")
      (node (ref "K4") (pin "B3") (pinfunction "B3_B3") (pintype "passive"))
      (node (ref "K4") (pin "B6") (pinfunction "B6_B6") (pintype "passive"))
    )
    (net (code "46") (name "Net-(LED1-C)") (class "Default")
      (node (ref "LED1") (pin "K") (pinfunction "C_K") (pintype "passive"))
      (node (ref "R2") (pin "1") (pinfunction "1_1") (pintype "passive"))
    )
    (net (code "47") (name "Net-(LED2-C)") (class "Default")
      (node (ref "LED2") (pin "K") (pinfunction "C_K") (pintype "passive"))
      (node (ref "R3") (pin "1") (pinfunction "1_1") (pintype "passive"))
    )
    (net (code "48") (name "Net-(LED3-C)") (class "Default")
      (node (ref "LED3") (pin "K") (pinfunction "C_K") (pintype "passive"))
      (node (ref "R4") (pin "1") (pinfunction "1_1") (pintype "passive"))
    )
    (net (code "49") (name "Net-(LED5-C)") (class "Default")
      (node (ref "LED5") (pin "K") (pinfunction "C_K") (pintype "passive"))
      (node (ref "R6") (pin "2") (pinfunction "2_2") (pintype "passive"))
    )
    (net (code "50") (name "Net-(LED6-C)") (class "Default")
      (node (ref "LED6") (pin "K") (pinfunction "C_K") (pintype "passive"))
      (node (ref "R7") (pin "2") (pinfunction "2_2") (pintype "passive"))
    )
    (net (code "51") (name "Net-(LED7-C)") (class "Default")
      (node (ref "LED7") (pin "K") (pinfunction "C_K") (pintype "passive"))
      (node (ref "R8") (pin "2") (pinfunction "2_2") (pintype "passive"))
    )
    (net (code "52") (name "Net-(LED8-C)") (class "Default")
      (node (ref "LED8") (pin "K") (pinfunction "C_K") (pintype "passive"))
      (node (ref "R9") (pin "2") (pinfunction "2_2") (pintype "passive"))
    )
    (net (code "53") (name "Net-(LED9-C)") (class "Default")
      (node (ref "LED9") (pin "K") (pinfunction "C_K") (pintype "passive"))
      (node (ref "R10") (pin "2") (pinfunction "2_2") (pintype "passive"))
    )
    (net (code "54") (name "P1") (class "Default")
      (node (ref "D1") (pin "C") (pinfunction "C_C") (pintype "passive"))
      (node (ref "K1") (pin "A3") (pinfunction "A3_A3") (pintype "passive"))
      (node (ref "K1") (pin "A6") (pinfunction "A6_A6") (pintype "passive"))
      (node (ref "K1") (pin "H3") (pinfunction "H3_H3") (pintype "passive"))
      (node (ref "K1") (pin "H6") (pinfunction "H6_H6") (pintype "passive"))
      (node (ref "LED8") (pin "A") (pinfunction "A_A") (pintype "passive"))
      (node (ref "R18") (pin "2") (pinfunction "2_2") (pintype "passive"))
    )
    (net (code "55") (name "P2") (class "Default")
      (node (ref "D2") (pin "C") (pinfunction "C_C") (pintype "passive"))
      (node (ref "K1") (pin "B3") (pinfunction "B3_B3") (pintype "passive"))
      (node (ref "K1") (pin "B6") (pinfunction "B6_B6") (pintype "passive"))
      (node (ref "K1") (pin "G3") (pinfunction "G3_G3") (pintype "passive"))
      (node (ref "K1") (pin "G6") (pinfunction "G6_G6") (pintype "passive"))
      (node (ref "LED7") (pin "A") (pinfunction "A_A") (pintype "passive"))
      (node (ref "R19") (pin "2") (pinfunction "2_2") (pintype "passive"))
    )
    (net (code "56") (name "P3") (class "Default")
      (node (ref "D3") (pin "C") (pinfunction "C_C") (pintype "passive"))
      (node (ref "K1") (pin "C3") (pinfunction "C3_C3") (pintype "passive"))
      (node (ref "K1") (pin "C6") (pinfunction "C6_C6") (pintype "passive"))
      (node (ref "K1") (pin "F3") (pinfunction "F3_F3") (pintype "passive"))
      (node (ref "K1") (pin "F6") (pinfunction "F6_F6") (pintype "passive"))
      (node (ref "LED6") (pin "A") (pinfunction "A_A") (pintype "passive"))
      (node (ref "R20") (pin "2") (pinfunction "2_2") (pintype "passive"))
    )
    (net (code "57") (name "P4") (class "Default")
      (node (ref "D8") (pin "C") (pinfunction "C_C") (pintype "passive"))
      (node (ref "K1") (pin "D3") (pinfunction "D3_D3") (pintype "passive"))
      (node (ref "K1") (pin "D6") (pinfunction "D6_D6") (pintype "passive"))
      (node (ref "K1") (pin "E3") (pinfunction "E3_E3") (pintype "passive"))
      (node (ref "K1") (pin "E6") (pinfunction "E6_E6") (pintype "passive"))
      (node (ref "LED5") (pin "A") (pinfunction "A_A") (pintype "passive"))
      (node (ref "R21") (pin "2") (pinfunction "2_2") (pintype "passive"))
    )
    (net (code "58") (name "P5V") (class "Default")
      (node (ref "C2") (pin "+") (pinfunction "+_+") (pintype "passive"))
      (node (ref "C3") (pin "1") (pinfunction "1_1") (pintype "passive"))
      (node (ref "C4") (pin "1") (pinfunction "1_1") (pintype "passive"))
      (node (ref "C7") (pin "1") (pinfunction "1_1") (pintype "passive"))
      (node (ref "IC2") (pin "3") (pinfunction "VDD_3") (pintype "power_in"))
      (node (ref "IC3") (pin "8") (pinfunction "VCC_8") (pintype "power_in"))
      (node (ref "JP4") (pin "1") (pinfunction "1_1") (pintype "passive"))
      (node (ref "K2") (pin "A1") (pinfunction "VCC_A1") (pintype "bidirectional"))
      (node (ref "K2") (pin "B1") (pinfunction "VCC_B1") (pintype "bidirectional"))
      (node (ref "K3") (pin "A1") (pinfunction "VCC_A1") (pintype "bidirectional"))
      (node (ref "K3") (pin "B1") (pinfunction "VCC_B1") (pintype "bidirectional"))
      (node (ref "MOD1") (pin "V+OUT1") (pinfunction "V+OUT1_V+OUT1") (pintype "bidirectional"))
      (node (ref "MOD1") (pin "V+OUT2") (pinfunction "V+OUT2_V+OUT2") (pintype "bidirectional"))
      (node (ref "U$1") (pin "18") (pinfunction "VDD_18") (pintype "power_in"))
      (node (ref "U$2") (pin "21") (pinfunction "VCC_21") (pintype "bidirectional"))
    )
    (net (code "59") (name "P24P") (class "Default")
      (node (ref "CON2") (pin "3") (pinfunction "3_3") (pintype "passive"))
      (node (ref "CON2") (pin "6") (pinfunction "6_6") (pintype "passive"))
      (node (ref "J1") (pin "1") (pinfunction "1_1") (pintype "passive"))
      (node (ref "J10") (pin "1") (pinfunction "1_1") (pintype "passive"))
      (node (ref "J2") (pin "1") (pinfunction "1_1") (pintype "passive"))
      (node (ref "J3") (pin "1") (pinfunction "1_1") (pintype "passive"))
      (node (ref "J4") (pin "1") (pinfunction "1_1") (pintype "passive"))
      (node (ref "J6") (pin "1") (pinfunction "1_1") (pintype "passive"))
      (node (ref "J7") (pin "1") (pinfunction "1_1") (pintype "passive"))
      (node (ref "J8") (pin "1") (pinfunction "1_1") (pintype "passive"))
      (node (ref "J9") (pin "1") (pinfunction "1_1") (pintype "passive"))
      (node (ref "JP4") (pin "8") (pinfunction "8_8") (pintype "passive"))
      (node (ref "R16") (pin "2") (pinfunction "2_2") (pintype "passive"))
    )
    (net (code "60") (name "RX") (class "Default")
      (node (ref "IC3") (pin "4") (pinfunction "DI_4") (pintype "input"))
      (node (ref "U$2") (pin "2") (pinfunction "RXI_2") (pintype "bidirectional"))
    )
    (net (code "61") (name "SCK") (class "Default")
      (node (ref "U$1") (pin "13") (pinfunction "SCK_13") (pintype "input"))
      (node (ref "U$2") (pin "16") (pinfunction "13_16") (pintype "bidirectional"))
    )
    (net (code "62") (name "SCL") (class "Default")
      (node (ref "JP4") (pin "5") (pinfunction "5_5") (pintype "passive"))
      (node (ref "U$2") (pin "A5") (pinfunction "A5_A5") (pintype "bidirectional"))
    )
    (net (code "63") (name "SDA") (class "Default")
      (node (ref "JP4") (pin "3") (pinfunction "3_3") (pintype "passive"))
      (node (ref "U$2") (pin "A4") (pinfunction "A4_A4") (pintype "bidirectional"))
    )
    (net (code "64") (name "SS") (class "Default")
      (node (ref "U$1") (pin "16") (pinfunction "~{CS}_16") (pintype "input"))
      (node (ref "U$2") (pin "13") (pinfunction "*10_13") (pintype "bidirectional"))
    )
    (net (code "65") (name "TX") (class "Default")
      (node (ref "IC3") (pin "1") (pinfunction "RO_1") (pintype "output"))
      (node (ref "U$2") (pin "1") (pinfunction "TXO_1") (pintype "bidirectional"))
    )
    (net (code "66") (name "unconnected-(IC1A-VREF-Pad5)") (class "Default")
      (node (ref "IC1") (pin "5") (pinfunction "VREF_5") (pintype "bidirectional"))
    )
    (net (code "67") (name "unconnected-(K2-D+-PadA3)") (class "Default")
      (node (ref "K2") (pin "A3") (pinfunction "D+_A3") (pintype "bidirectional"))
    )
    (net (code "68") (name "unconnected-(K2-D+-PadB3)") (class "Default")
      (node (ref "K2") (pin "B3") (pinfunction "D+_B3") (pintype "bidirectional"))
    )
    (net (code "69") (name "unconnected-(K2-D--PadA2)") (class "Default")
      (node (ref "K2") (pin "A2") (pinfunction "D-_A2") (pintype "bidirectional"))
    )
    (net (code "70") (name "unconnected-(K2-D--PadB2)") (class "Default")
      (node (ref "K2") (pin "B2") (pinfunction "D-_B2") (pintype "bidirectional"))
    )
    (net (code "71") (name "unconnected-(K3-D+-PadA3)") (class "Default")
      (node (ref "K3") (pin "A3") (pinfunction "D+_A3") (pintype "bidirectional"))
    )
    (net (code "72") (name "unconnected-(K3-D+-PadB3)") (class "Default")
      (node (ref "K3") (pin "B3") (pinfunction "D+_B3") (pintype "bidirectional"))
    )
    (net (code "73") (name "unconnected-(K3-D--PadA2)") (class "Default")
      (node (ref "K3") (pin "A2") (pinfunction "D-_A2") (pintype "bidirectional"))
    )
    (net (code "74") (name "unconnected-(K3-D--PadB2)") (class "Default")
      (node (ref "K3") (pin "B2") (pinfunction "D-_B2") (pintype "bidirectional"))
    )
    (net (code "75") (name "unconnected-(U$1-CLKOUT{slash}SOF-Pad3)") (class "Default")
      (node (ref "U$1") (pin "3") (pinfunction "CLKOUT/SOF_3") (pintype "output"))
    )
    (net (code "76") (name "unconnected-(U$1-~{INT}-Pad12)") (class "Default")
      (node (ref "U$1") (pin "12") (pinfunction "~{INT}_12") (pintype "output"))
    )
    (net (code "77") (name "unconnected-(U$1-~{RESET}-Pad17)") (class "Default")
      (node (ref "U$1") (pin "17") (pinfunction "~{RESET}_17") (pintype "input"))
    )
    (net (code "78") (name "unconnected-(U$1-~{RX0BF}-Pad11)") (class "Default")
      (node (ref "U$1") (pin "11") (pinfunction "~{RX0BF}_11") (pintype "output"))
    )
    (net (code "79") (name "unconnected-(U$1-~{RX1BF}-Pad10)") (class "Default")
      (node (ref "U$1") (pin "10") (pinfunction "~{RX1BF}_10") (pintype "output"))
    )
    (net (code "80") (name "unconnected-(U$1-~{TX0RTS}-Pad4)") (class "Default")
      (node (ref "U$1") (pin "4") (pinfunction "~{TX0RTS}_4") (pintype "input"))
    )
    (net (code "81") (name "unconnected-(U$1-~{TX1RTS}-Pad5)") (class "Default")
      (node (ref "U$1") (pin "5") (pinfunction "~{TX1RTS}_5") (pintype "input"))
    )
    (net (code "82") (name "unconnected-(U$1-~{TX2RTS}-Pad6)") (class "Default")
      (node (ref "U$1") (pin "6") (pinfunction "~{TX2RTS}_6") (pintype "input"))
    )
    (net (code "83") (name "unconnected-(U$2-RAW-Pad24)") (class "Default")
      (node (ref "U$2") (pin "24") (pinfunction "RAW_24") (pintype "bidirectional"))
    )
    (net (code "84") (name "unconnected-(U$2-RST-Pad22)") (class "Default")
      (node (ref "U$2") (pin "22") (pinfunction "RST_22") (pintype "bidirectional"))
    )
  )
)
